# MCU.net
KiCad netlist of a schematic drawn in Altium Designer
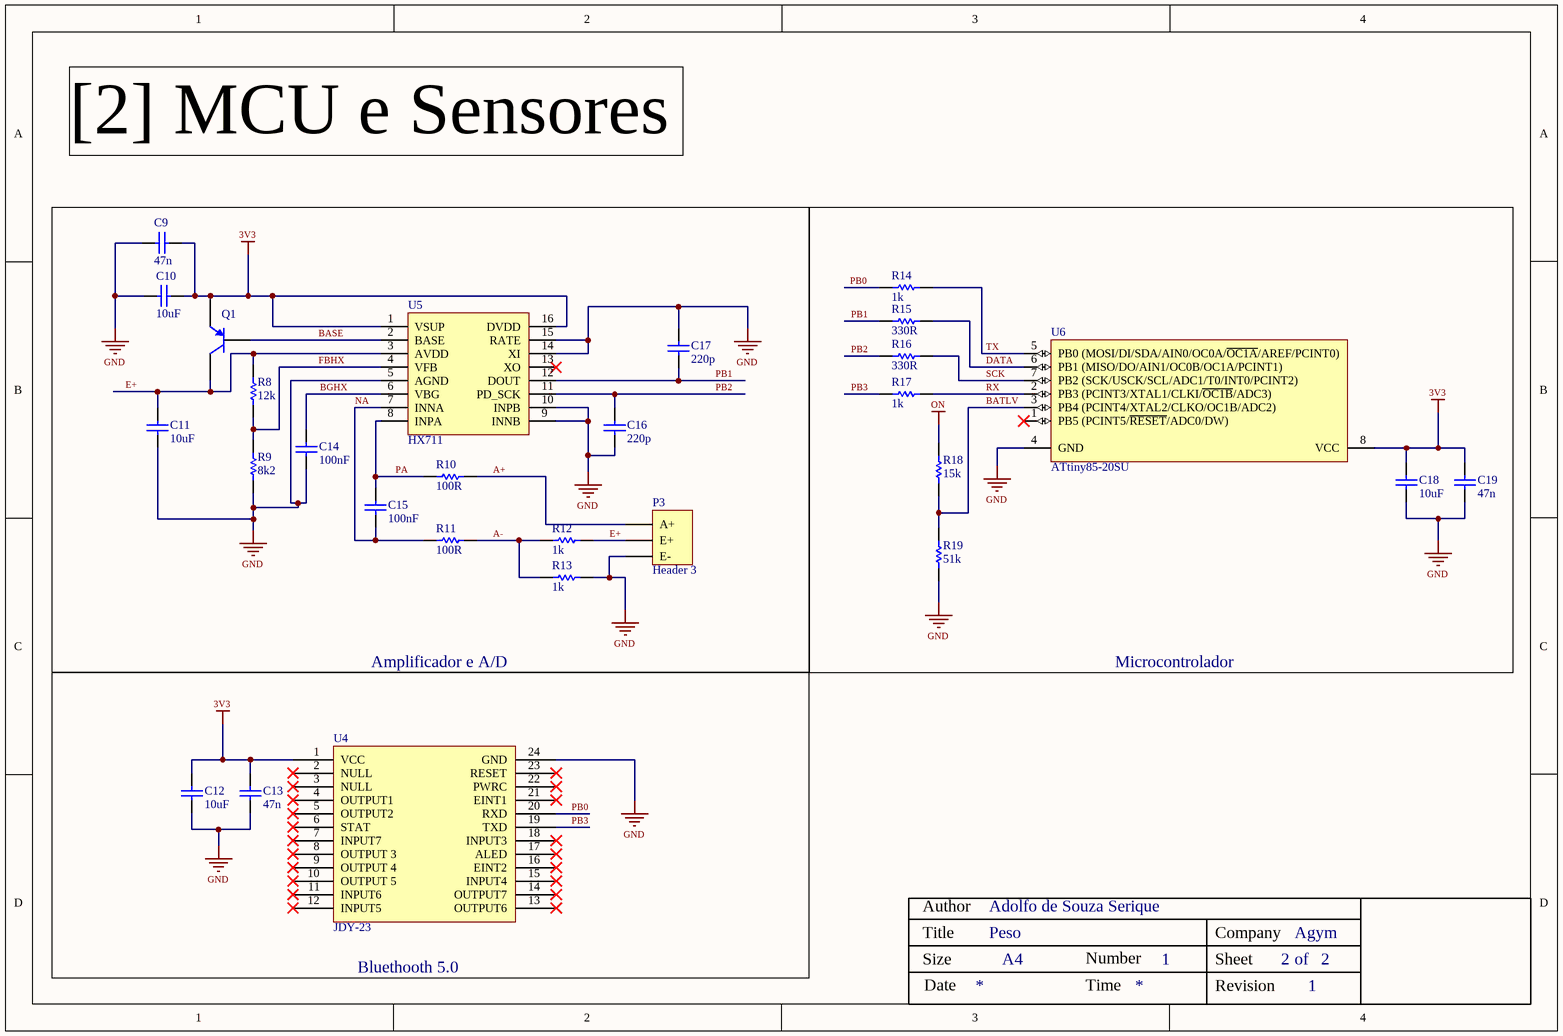
[diagram p0: MCU.SchDoc]

(export (version "E")
  (design (tool "Eeschema 10.0.6"))
  (components
    (comp (ref "C9")
      (value "47n")
      (footprint "C1608[0603]")
      (description "Prices include import duty and tax. CAP, 0.047UF, 50V, MLCC, 0603; SVHC: No SVHC (15-Jan-2019)")
      (fields (field (name "MANUFACTURER PART NUMBER") "CL10B473KB8NNNC") (field (name "TOLERANCE") "10%"))
      (libsource (lib "Basic Library") (part "C"))
    )
    (comp (ref "C10")
      (value "10uF")
      (footprint "C1608[0603]")
      (description "Cap Ceramic 10uF 10V X7R 20% Pad SMD 0603 125C T/R")
      (fields
        (field (name "MANUFACTURER PART NUMBER") "GRM188Z71A106MA73D")
        (field (name "LCSC PART NUMBER") "C237435")
      )
      (libsource (lib "Basic Library") (part "C"))
    )
    (comp (ref "C11")
      (value "10uF")
      (footprint "C1608[0603]")
      (description "Cap Ceramic 10uF 10V X7R 20% Pad SMD 0603 125C T/R")
      (fields
        (field (name "MANUFACTURER PART NUMBER") "GRM188Z71A106MA73D")
        (field (name "LCSC PART NUMBER") "C237435")
      )
      (libsource (lib "Basic Library") (part "C"))
    )
    (comp (ref "C12")
      (value "10uF")
      (footprint "C1608[0603]")
      (description "Cap Ceramic 10uF 10V X7R 20% Pad SMD 0603 125C T/R")
      (fields
        (field (name "MANUFACTURER PART NUMBER") "GRM188Z71A106MA73D")
        (field (name "LCSC PART NUMBER") "C237435")
      )
      (libsource (lib "Basic Library") (part "C"))
    )
    (comp (ref "C13")
      (value "47n")
      (footprint "C1608[0603]")
      (description "Prices include import duty and tax. CAP, 0.047UF, 50V, MLCC, 0603; SVHC: No SVHC (15-Jan-2019)")
      (fields (field (name "MANUFACTURER PART NUMBER") "CL10B473KB8NNNC") (field (name "TOLERANCE") "10%"))
      (libsource (lib "Basic Library") (part "C"))
    )
    (comp (ref "C14")
      (value "100nF")
      (footprint "C1608[0603]")
      (description "0603 0.1 uF 16 V ±10% Tolerance X7R Multilayer Ceramic Chip Capacitor")
      (fields (field (name "MANUFACTURER PART NUMBER") "GRM188R71C104KA01D") (field (name "TOLERANCE") "10%"))
      (libsource (lib "Basic Library") (part "C"))
    )
    (comp (ref "C15")
      (value "100nF")
      (footprint "C1608[0603]")
      (description "0603 0.1 uF 16 V ±10% Tolerance X7R Multilayer Ceramic Chip Capacitor")
      (fields (field (name "MANUFACTURER PART NUMBER") "GRM188R71C104KA01D") (field (name "TOLERANCE") "10%"))
      (libsource (lib "Basic Library") (part "C"))
    )
    (comp (ref "C16")
      (value "220p")
      (footprint "C1005[0402]")
      (description "CL05 Series 220 pF 50 V ±5 % Tolerance C0G SMT Multilayer Ceramic Capacitor")
      (fields (field (name "MANUFACTURER PART NUMBER") "CL05C221JB5NNNC") (field (name "TOLERANCE") "5%"))
      (libsource (lib "Basic Library") (part "C"))
    )
    (comp (ref "C17")
      (value "220p")
      (footprint "C1005[0402]")
      (description "CL05 Series 220 pF 50 V ±5 % Tolerance C0G SMT Multilayer Ceramic Capacitor")
      (fields (field (name "MANUFACTURER PART NUMBER") "CL05C221JB5NNNC") (field (name "TOLERANCE") "5%"))
      (libsource (lib "Basic Library") (part "C"))
    )
    (comp (ref "C18")
      (value "10uF")
      (footprint "C1608[0603]")
      (description "Cap Ceramic 10uF 10V X7R 20% Pad SMD 0603 125C T/R")
      (fields
        (field (name "MANUFACTURER PART NUMBER") "GRM188Z71A106MA73D")
        (field (name "LCSC PART NUMBER") "C237435")
      )
      (libsource (lib "Basic Library") (part "C"))
    )
    (comp (ref "C19")
      (value "47n")
      (footprint "C1608[0603]")
      (description "Prices include import duty and tax. CAP, 0.047UF, 50V, MLCC, 0603; SVHC: No SVHC (15-Jan-2019)")
      (fields (field (name "MANUFACTURER PART NUMBER") "CL10B473KB8NNNC") (field (name "TOLERANCE") "10%"))
      (libsource (lib "Basic Library") (part "C"))
    )
    (comp (ref "P3")
      (value "Header 3")
      (footprint "HDR1X3")
      (description "Header, 3-Pin")
      (fields (field (name "PUBLISHER") "Altium Limited"))
      (libsource (lib "Miscellaneous Connectors") (part "Header 3"))
    )
    (comp (ref "Q1")
      (value "PNP")
      (footprint "SOT-23-3")
      (description "Transistor Bipolar SOT-23 25V 300mW 500mA PNP")
      (fields
        (field (name "MANUFACTURER") "Jiangsu Changjing Electronics Technology Co., Ltd.")
        (field (name "MANUFACTURER PART NUMBER") "S8550-2TY")
      )
      (libsource (lib "Minha_Biblioteca") (part "S8550-2TY"))
    )
    (comp (ref "R8")
      (value "12k")
      (footprint "R1608[0603]")
      (description "Res Thick Film 0603 12K Ohm 0.5% 1/16W ±50ppm/°C Molded SMD Punched Carrier T/R")
      (fields (field (name "MANUFACTURER PART NUMBER") "ERJ3RBD1202V") (field (name "TOLERANCE") "0.5%"))
      (libsource (lib "Basic Library") (part "R"))
    )
    (comp (ref "R9")
      (value "8k2")
      (footprint "R1608[0603]")
      (description "Resistor")
      (fields
        (field (name "MANUFACTURER") "PANASONIC")
        (field (name "MANUFACTURER PART NUMBER") "ERA3VEB8201V")
      )
      (libsource (lib "Basic Library") (part "R"))
    )
    (comp (ref "R10")
      (value "100R")
      (footprint "R1608[0603]")
      (description "Res Thin Film 0603 100 Ohm 0.1% 1/10W ±25ppm/°C Molded SMD SMD Punched Carrier T/R")
      (fields (field (name "MANUFACTURER PART NUMBER") "ERA-3AEB101V") (field (name "TOLERANCE") "0.1%"))
      (libsource (lib "Basic Library") (part "R"))
    )
    (comp (ref "R11")
      (value "100R")
      (footprint "R1608[0603]")
      (description "Res Thin Film 0603 100 Ohm 0.1% 1/10W ±25ppm/°C Molded SMD SMD Punched Carrier T/R")
      (fields (field (name "MANUFACTURER PART NUMBER") "ERA-3AEB101V") (field (name "TOLERANCE") "0.1%"))
      (libsource (lib "Basic Library") (part "R"))
    )
    (comp (ref "R12")
      (value "1k")
      (footprint "R1608[0603]")
      (description "ERJ Series 0603 1 kOhm 0.2 W ±0.1 % ±50ppm/°C Thick Film Chip Resistor")
      (fields (field (name "MANUFACTURER PART NUMBER") "ERJ-PB3B1001V") (field (name "TOLERANCE") "0.1%"))
      (libsource (lib "Basic Library") (part "R"))
    )
    (comp (ref "R13")
      (value "1k")
      (footprint "R1608[0603]")
      (description "ERJ Series 0603 1 kOhm 0.2 W ±0.1 % ±50ppm/°C Thick Film Chip Resistor")
      (fields (field (name "MANUFACTURER PART NUMBER") "ERJ-PB3B1001V") (field (name "TOLERANCE") "0.1%"))
      (libsource (lib "Basic Library") (part "R"))
    )
    (comp (ref "R14")
      (value "1k")
      (footprint "R1608[0603]")
      (description "ERJ Series 0603 1 kOhm 0.2 W ±0.1 % ±50ppm/°C Thick Film Chip Resistor")
      (fields (field (name "MANUFACTURER PART NUMBER") "ERJ-PB3B1001V") (field (name "TOLERANCE") "0.1%"))
      (libsource (lib "Basic Library") (part "R"))
    )
    (comp (ref "R15")
      (value "330R")
      (footprint "R1608[0603]")
      (description "Res Thick Film 0603 330 Ohm 1% 1/10W +/-100ppm/ßC Molded SMD Punched Carrier T/R")
      (fields (field (name "MANUFACTURER PART NUMBER") "ERJ3EKF3300V") (field (name "TOLERANCE") "1%"))
      (libsource (lib "Basic Library") (part "R"))
    )
    (comp (ref "R16")
      (value "330R")
      (footprint "R1608[0603]")
      (description "Res Thick Film 0603 330 Ohm 1% 1/10W +/-100ppm/ßC Molded SMD Punched Carrier T/R")
      (fields (field (name "MANUFACTURER PART NUMBER") "ERJ3EKF3300V") (field (name "TOLERANCE") "1%"))
      (libsource (lib "Basic Library") (part "R"))
    )
    (comp (ref "R17")
      (value "1k")
      (footprint "R1608[0603]")
      (description "ERJ Series 0603 1 kOhm 0.2 W ±0.1 % ±50ppm/°C Thick Film Chip Resistor")
      (fields (field (name "MANUFACTURER PART NUMBER") "ERJ-PB3B1001V") (field (name "TOLERANCE") "0.1%"))
      (libsource (lib "Basic Library") (part "R"))
    )
    (comp (ref "R18")
      (value "15k")
      (footprint "R1608[0603]")
      (description "Res Thick Film 0603 15K Ohm 1% 1/10W ±100ppm/°C SMD Punched Carrier T/R")
      (fields (field (name "MANUFACTURER PART NUMBER") "ERJ-3EKF1502V") (field (name "TOLERANCE") "1%"))
      (libsource (lib "Basic Library") (part "R"))
    )
    (comp (ref "R19")
      (value "51k")
      (footprint "R1608[0603]")
      (description "Res Thick Film 0603 51K Ohm 1% 1/10W ±100ppm/°C Molded SMD Punched Carrier T/R")
      (fields (field (name "MANUFACTURER PART NUMBER") "ERJ-3EKF5102V") (field (name "TOLERANCE") "1%"))
      (libsource (lib "Basic Library") (part "R"))
    )
    (comp (ref "U4")
      (value "JDY-23")
      (footprint "JDY")
      (description "BD Module")
      (libsource (lib "Minha_Biblioteca") (part "JDY-23"))
    )
    (comp (ref "U5")
      (value "HX711")
      (footprint "SOP-16-150mil")
      (description "Amplificador e A/D")
      (fields
        (field (name "MANUFACTURER") "Avia Semicon (Xiamen)")
        (field (name "LCSC PART NUMBER") "C43656")
      )
      (libsource (lib "Minha_Biblioteca") (part "HX711"))
    )
    (comp (ref "U6")
      (value "ATtiny85-20SU")
      (footprint "8S2_L")
      (libsource (lib "Atmel Microcontroller tinyAVR") (part "ATtiny85-20SU"))
    )
  )
  (nets
    (net (code "1") (name "/A+") (class "Default")
      (node (ref "P3") (pin "3") (pinfunction "A+_3") (pintype "passive"))
      (node (ref "R10") (pin "2") (pinfunction "2_2") (pintype "passive"))
    )
    (net (code "2") (name "/A-") (class "Default")
      (node (ref "R11") (pin "2") (pinfunction "2_2") (pintype "passive"))
      (node (ref "R12") (pin "1") (pinfunction "1_1") (pintype "passive"))
      (node (ref "R13") (pin "2") (pinfunction "2_2") (pintype "passive"))
    )
    (net (code "3") (name "/BASE") (class "Default")
      (node (ref "Q1") (pin "1") (pinfunction "B_1") (pintype "passive"))
      (node (ref "U5") (pin "2") (pinfunction "BASE_2") (pintype "passive"))
    )
    (net (code "4") (name "/BATLV") (class "Default")
      (node (ref "R18") (pin "1") (pinfunction "1_1") (pintype "passive"))
      (node (ref "R19") (pin "2") (pinfunction "2_2") (pintype "passive"))
      (node (ref "U6") (pin "3") (pinfunction "PB4_(PCINT4/XTAL2/CLKO/OC1B/ADC2)_3") (pintype "bidirectional"))
    )
    (net (code "5") (name "/BGHX") (class "Default")
      (node (ref "C14") (pin "2") (pinfunction "2_2") (pintype "passive"))
      (node (ref "U5") (pin "6") (pinfunction "VBG_6") (pintype "passive"))
    )
    (net (code "6") (name "/DATA") (class "Default")
      (node (ref "R15") (pin "2") (pinfunction "2_2") (pintype "passive"))
      (node (ref "U6") (pin "6") (pinfunction "PB1_(MISO/DO/AIN1/OC0B/OC1A/PCINT1)_6") (pintype "bidirectional"))
    )
    (net (code "7") (name "/E+") (class "Default")
      (node (ref "C11") (pin "2") (pinfunction "2_2") (pintype "passive"))
      (node (ref "P3") (pin "1") (pinfunction "E+_1") (pintype "passive"))
      (node (ref "Q1") (pin "3") (pinfunction "C_3") (pintype "passive"))
      (node (ref "R12") (pin "2") (pinfunction "2_2") (pintype "passive"))
      (node (ref "R8") (pin "2") (pinfunction "2_2") (pintype "passive"))
      (node (ref "U5") (pin "3") (pinfunction "AVDD_3") (pintype "passive"))
    )
    (net (code "8") (name "/FBHX") (class "Default")
      (node (ref "R8") (pin "1") (pinfunction "1_1") (pintype "passive"))
      (node (ref "R9") (pin "2") (pinfunction "2_2") (pintype "passive"))
      (node (ref "U5") (pin "4") (pinfunction "VFB_4") (pintype "passive"))
    )
    (net (code "9") (name "/NA") (class "Default")
      (node (ref "C15") (pin "1") (pinfunction "1_1") (pintype "passive"))
      (node (ref "R11") (pin "1") (pinfunction "1_1") (pintype "passive"))
      (node (ref "U5") (pin "7") (pinfunction "INNA_7") (pintype "passive"))
    )
    (net (code "10") (name "/PA") (class "Default")
      (node (ref "C15") (pin "2") (pinfunction "2_2") (pintype "passive"))
      (node (ref "R10") (pin "1") (pinfunction "1_1") (pintype "passive"))
      (node (ref "U5") (pin "8") (pinfunction "INPA_8") (pintype "passive"))
    )
    (net (code "11") (name "/PB0") (class "Default")
      (node (ref "R14") (pin "1") (pinfunction "1_1") (pintype "passive"))
      (node (ref "U4") (pin "20") (pinfunction "RXD_20") (pintype "passive"))
    )
    (net (code "12") (name "/PB1") (class "Default")
      (node (ref "C17") (pin "1") (pinfunction "1_1") (pintype "passive"))
      (node (ref "R15") (pin "1") (pinfunction "1_1") (pintype "passive"))
      (node (ref "U5") (pin "12") (pinfunction "DOUT_12") (pintype "passive"))
    )
    (net (code "13") (name "/PB2") (class "Default")
      (node (ref "C16") (pin "2") (pinfunction "2_2") (pintype "passive"))
      (node (ref "R16") (pin "1") (pinfunction "1_1") (pintype "passive"))
      (node (ref "U5") (pin "11") (pinfunction "PD_SCK_11") (pintype "passive"))
    )
    (net (code "14") (name "/PB3") (class "Default")
      (node (ref "R17") (pin "1") (pinfunction "1_1") (pintype "passive"))
      (node (ref "U4") (pin "19") (pinfunction "TXD_19") (pintype "passive"))
    )
    (net (code "15") (name "/RX") (class "Default")
      (node (ref "R17") (pin "2") (pinfunction "2_2") (pintype "passive"))
      (node (ref "U6") (pin "2") (pinfunction "PB3_(PCINT3/XTAL1/CLKI/~{OC1B}/ADC3)_2") (pintype "bidirectional"))
    )
    (net (code "16") (name "/SCK") (class "Default")
      (node (ref "R16") (pin "2") (pinfunction "2_2") (pintype "passive"))
      (node (ref "U6") (pin "7") (pinfunction "PB2_(SCK/USCK/SCL/ADC1/T0/INT0/PCINT2)_7") (pintype "bidirectional"))
    )
    (net (code "17") (name "/TX") (class "Default")
      (node (ref "R14") (pin "2") (pinfunction "2_2") (pintype "passive"))
      (node (ref "U6") (pin "5") (pinfunction "PB0_(MOSI/DI/SDA/AIN0/OC0A/~{OC1A}/AREF/PCINT0)_5") (pintype "bidirectional"))
    )
    (net (code "18") (name "3V3") (class "Default")
      (node (ref "C10") (pin "2") (pinfunction "2_2") (pintype "passive"))
      (node (ref "C12") (pin "1") (pinfunction "1_1") (pintype "passive"))
      (node (ref "C13") (pin "2") (pinfunction "2_2") (pintype "passive"))
      (node (ref "C18") (pin "1") (pinfunction "1_1") (pintype "passive"))
      (node (ref "C19") (pin "2") (pinfunction "2_2") (pintype "passive"))
      (node (ref "C9") (pin "2") (pinfunction "2_2") (pintype "passive"))
      (node (ref "Q1") (pin "2") (pinfunction "E_2") (pintype "passive"))
      (node (ref "U4") (pin "1") (pinfunction "VCC_1") (pintype "passive"))
      (node (ref "U5") (pin "1") (pinfunction "VSUP_1") (pintype "passive"))
      (node (ref "U5") (pin "16") (pinfunction "DVDD_16") (pintype "passive"))
      (node (ref "U6") (pin "8") (pinfunction "VCC_8") (pintype "power_in"))
    )
    (net (code "19") (name "GND") (class "Default")
      (node (ref "C10") (pin "1") (pinfunction "1_1") (pintype "passive"))
      (node (ref "C11") (pin "1") (pinfunction "1_1") (pintype "passive"))
      (node (ref "C12") (pin "2") (pinfunction "2_2") (pintype "passive"))
      (node (ref "C13") (pin "1") (pinfunction "1_1") (pintype "passive"))
      (node (ref "C14") (pin "1") (pinfunction "1_1") (pintype "passive"))
      (node (ref "C16") (pin "1") (pinfunction "1_1") (pintype "passive"))
      (node (ref "C17") (pin "2") (pinfunction "2_2") (pintype "passive"))
      (node (ref "C18") (pin "2") (pinfunction "2_2") (pintype "passive"))
      (node (ref "C19") (pin "1") (pinfunction "1_1") (pintype "passive"))
      (node (ref "C9") (pin "1") (pinfunction "1_1") (pintype "passive"))
      (node (ref "P3") (pin "2") (pinfunction "E-_2") (pintype "passive"))
      (node (ref "R13") (pin "1") (pinfunction "1_1") (pintype "passive"))
      (node (ref "R19") (pin "1") (pinfunction "1_1") (pintype "passive"))
      (node (ref "R9") (pin "1") (pinfunction "1_1") (pintype "passive"))
      (node (ref "U4") (pin "24") (pinfunction "GND_24") (pintype "passive"))
      (node (ref "U5") (pin "10") (pinfunction "INPB_10") (pintype "passive"))
      (node (ref "U5") (pin "14") (pinfunction "XI_14") (pintype "passive"))
      (node (ref "U5") (pin "15") (pinfunction "RATE_15") (pintype "passive"))
      (node (ref "U5") (pin "5") (pinfunction "AGND_5") (pintype "passive"))
      (node (ref "U5") (pin "9") (pinfunction "INNB_9") (pintype "passive"))
      (node (ref "U6") (pin "4") (pinfunction "GND_4") (pintype "power_in"))
    )
    (net (code "20") (name "ON") (class "Default")
      (node (ref "R18") (pin "2") (pinfunction "2_2") (pintype "passive"))
    )
    (net (code "21") (name "unconnected-(U4-ALED-Pad17)") (class "Default")
      (node (ref "U4") (pin "17") (pinfunction "ALED_17") (pintype "passive+no_connect"))
    )
    (net (code "22") (name "unconnected-(U4-EINT1-Pad21)") (class "Default")
      (node (ref "U4") (pin "21") (pinfunction "EINT1_21") (pintype "passive+no_connect"))
    )
    (net (code "23") (name "unconnected-(U4-EINT2-Pad16)") (class "Default")
      (node (ref "U4") (pin "16") (pinfunction "EINT2_16") (pintype "passive+no_connect"))
    )
    (net (code "24") (name "unconnected-(U4-INPUT3-Pad18)") (class "Default")
      (node (ref "U4") (pin "18") (pinfunction "INPUT3_18") (pintype "passive+no_connect"))
    )
    (net (code "25") (name "unconnected-(U4-INPUT4-Pad15)") (class "Default")
      (node (ref "U4") (pin "15") (pinfunction "INPUT4_15") (pintype "passive+no_connect"))
    )
    (net (code "26") (name "unconnected-(U4-INPUT5-Pad12)") (class "Default")
      (node (ref "U4") (pin "12") (pinfunction "INPUT5_12") (pintype "passive+no_connect"))
    )
    (net (code "27") (name "unconnected-(U4-INPUT6-Pad11)") (class "Default")
      (node (ref "U4") (pin "11") (pinfunction "INPUT6_11") (pintype "passive+no_connect"))
    )
    (net (code "28") (name "unconnected-(U4-INPUT7-Pad7)") (class "Default")
      (node (ref "U4") (pin "7") (pinfunction "INPUT7_7") (pintype "passive+no_connect"))
    )
    (net (code "29") (name "unconnected-(U4-NULL-Pad2)") (class "Default")
      (node (ref "U4") (pin "2") (pinfunction "NULL_2") (pintype "passive+no_connect"))
    )
    (net (code "30") (name "unconnected-(U4-NULL-Pad3)") (class "Default")
      (node (ref "U4") (pin "3") (pinfunction "NULL_3") (pintype "passive+no_connect"))
    )
    (net (code "31") (name "unconnected-(U4-OUTPUT1-Pad4)") (class "Default")
      (node (ref "U4") (pin "4") (pinfunction "OUTPUT1_4") (pintype "passive+no_connect"))
    )
    (net (code "32") (name "unconnected-(U4-OUTPUT2-Pad5)") (class "Default")
      (node (ref "U4") (pin "5") (pinfunction "OUTPUT2_5") (pintype "passive+no_connect"))
    )
    (net (code "33") (name "unconnected-(U4-OUTPUT6-Pad13)") (class "Default")
      (node (ref "U4") (pin "13") (pinfunction "OUTPUT6_13") (pintype "passive+no_connect"))
    )
    (net (code "34") (name "unconnected-(U4-OUTPUT7-Pad14)") (class "Default")
      (node (ref "U4") (pin "14") (pinfunction "OUTPUT7_14") (pintype "passive+no_connect"))
    )
    (net (code "35") (name "unconnected-(U4-OUTPUT_3-Pad8)") (class "Default")
      (node (ref "U4") (pin "8") (pinfunction "OUTPUT_3_8") (pintype "passive+no_connect"))
    )
    (net (code "36") (name "unconnected-(U4-OUTPUT_4-Pad9)") (class "Default")
      (node (ref "U4") (pin "9") (pinfunction "OUTPUT_4_9") (pintype "passive+no_connect"))
    )
    (net (code "37") (name "unconnected-(U4-OUTPUT_5-Pad10)") (class "Default")
      (node (ref "U4") (pin "10") (pinfunction "OUTPUT_5_10") (pintype "passive+no_connect"))
    )
    (net (code "38") (name "unconnected-(U4-PWRC-Pad22)") (class "Default")
      (node (ref "U4") (pin "22") (pinfunction "PWRC_22") (pintype "passive+no_connect"))
    )
    (net (code "39") (name "unconnected-(U4-RESET-Pad23)") (class "Default")
      (node (ref "U4") (pin "23") (pinfunction "RESET_23") (pintype "passive+no_connect"))
    )
    (net (code "40") (name "unconnected-(U4-STAT-Pad6)") (class "Default")
      (node (ref "U4") (pin "6") (pinfunction "STAT_6") (pintype "passive+no_connect"))
    )
    (net (code "41") (name "unconnected-(U5-XO-Pad13)") (class "Default")
      (node (ref "U5") (pin "13") (pinfunction "XO_13") (pintype "passive+no_connect"))
    )
    (net (code "42") (name "unconnected-(U6-PB5_(PCINT5{slash}~{RESET}{slash}ADC0{slash}DW)-Pad1)") (class "Default")
      (node (ref "U6") (pin "1") (pinfunction "PB5_(PCINT5/~{RESET}/ADC0/DW)_1") (pintype "bidirectional+no_connect"))
    )
  )
)
